# SDLbeerlight.net
KiCad netlist of a schematic drawn in EAGLE
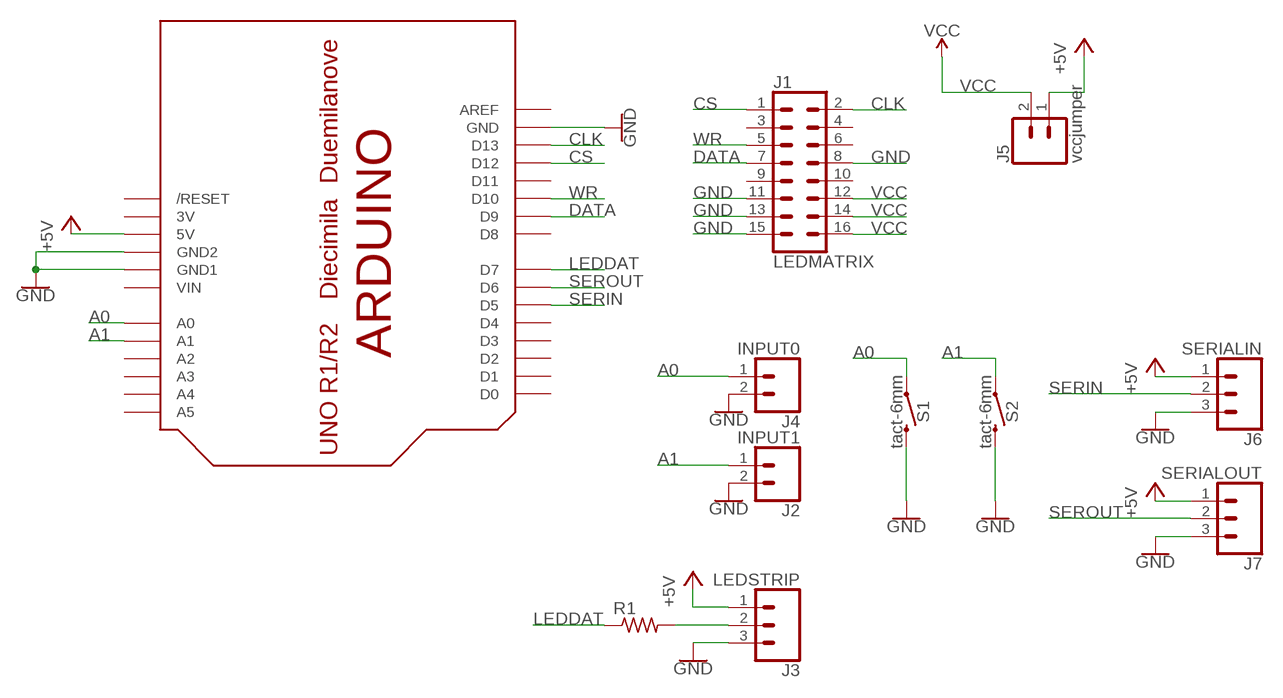
[diagram p0: schematic, sheet 1]

(export (version "E")
  (design (tool "Eeschema 10.0.6"))
  (components
    (comp (ref "J1")
      (value "LEDMATRIX")
      (footprint "eagle-import:2X8")
      (libsource (lib "eagle-import") (part "CONN_08X2"))
    )
    (comp (ref "J2")
      (value "INPUT1")
      (footprint "eagle-import:1X02_LONGPADS")
      (libsource (lib "eagle-import") (part "CONN_02PTH3"))
    )
    (comp (ref "J3")
      (value "LEDSTRIP")
      (footprint "eagle-import:1X03_LONGPADS")
      (libsource (lib "eagle-import") (part "CONN_03LONGPADS"))
    )
    (comp (ref "J4")
      (value "INPUT0")
      (footprint "eagle-import:1X02_LONGPADS")
      (libsource (lib "eagle-import") (part "CONN_02PTH3"))
    )
    (comp (ref "J5")
      (value "vccjumper")
      (footprint "eagle-import:1X02_LOCK_LONGPADS")
      (libsource (lib "eagle-import") (part "CONN_02LOCK_LONGPADS"))
    )
    (comp (ref "J6")
      (value "SERIALIN")
      (footprint "eagle-import:1X03_LONGPADS")
      (libsource (lib "eagle-import") (part "CONN_03LONGPADS"))
    )
    (comp (ref "J7")
      (value "SERIALOUT")
      (footprint "eagle-import:1X03_LONGPADS")
      (libsource (lib "eagle-import") (part "CONN_03LONGPADS"))
    )
    (comp (ref "R1")
      (value "R-US_0204/7")
      (footprint "eagle-import:0204_7")
      (libsource (lib "eagle-import") (part "R-US_0204/7"))
    )
    (comp (ref "S1")
      (value "tact-6mm")
      (footprint "eagle-import:TACTILE_SWITCH_PTH_6.0MM")
      (libsource (lib "eagle-import") (part "MOMENTARY-SWITCH-SPST-PTH-6.0MM"))
    )
    (comp (ref "S2")
      (value "tact-6mm")
      (footprint "eagle-import:TACTILE_SWITCH_PTH_6.0MM")
      (libsource (lib "eagle-import") (part "MOMENTARY-SWITCH-SPST-PTH-6.0MM"))
    )
    (comp (ref "U$2")
      (value "ARDUINOUNO")
      (footprint "eagle-import:ARDUINO")
      (libsource (lib "eagle-import") (part "ARDUINOUNO"))
    )
  )
  (nets
    (net (code "1") (name "+5V") (class "Default")
      (node (ref "J3") (pin "1") (pinfunction "1_1") (pintype "passive"))
      (node (ref "J5") (pin "1") (pinfunction "1_1") (pintype "passive"))
      (node (ref "J6") (pin "1") (pinfunction "1_1") (pintype "passive"))
      (node (ref "J7") (pin "1") (pinfunction "1_1") (pintype "passive"))
      (node (ref "U$2") (pin "5V") (pinfunction "5V_5V") (pintype "power_in"))
    )
    (net (code "2") (name "/3V") (class "Default")
      (node (ref "U$2") (pin "3V") (pinfunction "3V_3V") (pintype "power_in"))
    )
    (net (code "3") (name "/A0") (class "Default")
      (node (ref "J4") (pin "1") (pinfunction "1_1") (pintype "passive"))
      (node (ref "S1") (pin "1") (pinfunction "1_1") (pintype "passive"))
      (node (ref "U$2") (pin "A0") (pinfunction "A0_A0") (pintype "bidirectional"))
    )
    (net (code "4") (name "/A1") (class "Default")
      (node (ref "J2") (pin "1") (pinfunction "1_1") (pintype "passive"))
      (node (ref "S2") (pin "1") (pinfunction "1_1") (pintype "passive"))
      (node (ref "U$2") (pin "A1") (pinfunction "A1_A1") (pintype "bidirectional"))
    )
    (net (code "5") (name "/CLK") (class "Default")
      (node (ref "J1") (pin "2") (pinfunction "2_2") (pintype "passive"))
      (node (ref "U$2") (pin "D13") (pinfunction "D13_D13") (pintype "bidirectional"))
    )
    (net (code "6") (name "/CS") (class "Default")
      (node (ref "J1") (pin "1") (pinfunction "1_1") (pintype "passive"))
      (node (ref "U$2") (pin "D12") (pinfunction "D12_D12") (pintype "bidirectional"))
    )
    (net (code "7") (name "/DATA") (class "Default")
      (node (ref "J1") (pin "7") (pinfunction "7_7") (pintype "passive"))
      (node (ref "U$2") (pin "D9") (pinfunction "D9_D9") (pintype "bidirectional"))
    )
    (net (code "8") (name "/LEDDAT") (class "Default")
      (node (ref "R1") (pin "1") (pinfunction "1_1") (pintype "passive"))
      (node (ref "U$2") (pin "D7") (pinfunction "D7_D7") (pintype "bidirectional"))
    )
    (net (code "9") (name "/SERIN") (class "Default")
      (node (ref "J6") (pin "2") (pinfunction "2_2") (pintype "passive"))
      (node (ref "U$2") (pin "D5") (pinfunction "D5_D5") (pintype "bidirectional"))
    )
    (net (code "10") (name "/SEROUT") (class "Default")
      (node (ref "J7") (pin "2") (pinfunction "2_2") (pintype "passive"))
      (node (ref "U$2") (pin "D6") (pinfunction "D6_D6") (pintype "bidirectional"))
    )
    (net (code "11") (name "/VIN") (class "Default")
      (node (ref "U$2") (pin "VIN") (pinfunction "VIN_VIN") (pintype "power_in"))
    )
    (net (code "12") (name "/WR") (class "Default")
      (node (ref "J1") (pin "5") (pinfunction "5_5") (pintype "passive"))
      (node (ref "U$2") (pin "D10") (pinfunction "D10_D10") (pintype "bidirectional"))
    )
    (net (code "13") (name "GND") (class "Default")
      (node (ref "J1") (pin "11") (pinfunction "11_11") (pintype "passive"))
      (node (ref "J1") (pin "13") (pinfunction "13_13") (pintype "passive"))
      (node (ref "J1") (pin "15") (pinfunction "15_15") (pintype "passive"))
      (node (ref "J1") (pin "8") (pinfunction "8_8") (pintype "passive"))
      (node (ref "J2") (pin "2") (pinfunction "2_2") (pintype "passive"))
      (node (ref "J3") (pin "3") (pinfunction "3_3") (pintype "passive"))
      (node (ref "J4") (pin "2") (pinfunction "2_2") (pintype "passive"))
      (node (ref "J6") (pin "3") (pinfunction "3_3") (pintype "passive"))
      (node (ref "J7") (pin "3") (pinfunction "3_3") (pintype "passive"))
      (node (ref "S1") (pin "3") (pinfunction "2_3") (pintype "passive"))
      (node (ref "S2") (pin "3") (pinfunction "2_3") (pintype "passive"))
      (node (ref "U$2") (pin "GND") (pinfunction "GND_GND") (pintype "power_in"))
      (node (ref "U$2") (pin "GND1") (pinfunction "GND1_GND1") (pintype "power_in"))
      (node (ref "U$2") (pin "GND2") (pinfunction "GND2_GND2") (pintype "power_in"))
    )
    (net (code "14") (name "Net-(J3-Pad2)") (class "Default")
      (node (ref "J3") (pin "2") (pinfunction "2_2") (pintype "passive"))
      (node (ref "R1") (pin "2") (pinfunction "2_2") (pintype "passive"))
    )
    (net (code "15") (name "VCC") (class "Default")
      (node (ref "J1") (pin "12") (pinfunction "12_12") (pintype "passive"))
      (node (ref "J1") (pin "14") (pinfunction "14_14") (pintype "passive"))
      (node (ref "J1") (pin "16") (pinfunction "16_16") (pintype "passive"))
      (node (ref "J5") (pin "2") (pinfunction "2_2") (pintype "passive"))
    )
    (net (code "16") (name "unconnected-(J1-Pad3)") (class "Default")
      (node (ref "J1") (pin "3") (pinfunction "3_3") (pintype "passive"))
    )
    (net (code "17") (name "unconnected-(J1-Pad4)") (class "Default")
      (node (ref "J1") (pin "4") (pinfunction "4_4") (pintype "passive"))
    )
    (net (code "18") (name "unconnected-(J1-Pad6)") (class "Default")
      (node (ref "J1") (pin "6") (pinfunction "6_6") (pintype "passive"))
    )
    (net (code "19") (name "unconnected-(J1-Pad9)") (class "Default")
      (node (ref "J1") (pin "9") (pinfunction "9_9") (pintype "passive"))
    )
    (net (code "20") (name "unconnected-(J1-Pad10)") (class "Default")
      (node (ref "J1") (pin "10") (pinfunction "10_10") (pintype "passive"))
    )
    (net (code "21") (name "unconnected-(U$2-PadA2)") (class "Default")
      (node (ref "U$2") (pin "A2") (pinfunction "A2_A2") (pintype "bidirectional"))
    )
    (net (code "22") (name "unconnected-(U$2-PadA3)") (class "Default")
      (node (ref "U$2") (pin "A3") (pinfunction "A3_A3") (pintype "bidirectional"))
    )
    (net (code "23") (name "unconnected-(U$2-PadA4)") (class "Default")
      (node (ref "U$2") (pin "A4") (pinfunction "A4_A4") (pintype "bidirectional"))
    )
    (net (code "24") (name "unconnected-(U$2-PadA5)") (class "Default")
      (node (ref "U$2") (pin "A5") (pinfunction "A5_A5") (pintype "bidirectional"))
    )
    (net (code "25") (name "unconnected-(U$2-PadAREF)") (class "Default")
      (node (ref "U$2") (pin "AREF") (pinfunction "AREF_AREF") (pintype "bidirectional"))
    )
    (net (code "26") (name "unconnected-(U$2-PadD0)") (class "Default")
      (node (ref "U$2") (pin "D0") (pinfunction "D0_D0") (pintype "bidirectional"))
    )
    (net (code "27") (name "unconnected-(U$2-PadD1)") (class "Default")
      (node (ref "U$2") (pin "D1") (pinfunction "D1_D1") (pintype "bidirectional"))
    )
    (net (code "28") (name "unconnected-(U$2-PadD2)") (class "Default")
      (node (ref "U$2") (pin "D2") (pinfunction "D2_D2") (pintype "bidirectional"))
    )
    (net (code "29") (name "unconnected-(U$2-PadD3)") (class "Default")
      (node (ref "U$2") (pin "D3") (pinfunction "D3_D3") (pintype "bidirectional"))
    )
    (net (code "30") (name "unconnected-(U$2-PadD4)") (class "Default")
      (node (ref "U$2") (pin "D4") (pinfunction "D4_D4") (pintype "bidirectional"))
    )
    (net (code "31") (name "unconnected-(U$2-PadD8)") (class "Default")
      (node (ref "U$2") (pin "D8") (pinfunction "D8_D8") (pintype "bidirectional"))
    )
    (net (code "32") (name "unconnected-(U$2-PadD11)") (class "Default")
      (node (ref "U$2") (pin "D11") (pinfunction "D11_D11") (pintype "bidirectional"))
    )
    (net (code "33") (name "unconnected-(U$2-{slash}RESET-PadRESET)") (class "Default")
      (node (ref "U$2") (pin "RESET") (pinfunction "/RESET_RESET") (pintype "bidirectional"))
    )
  )
)
